# Power-Conversion.net
KiCad netlist of a schematic drawn in EAGLE
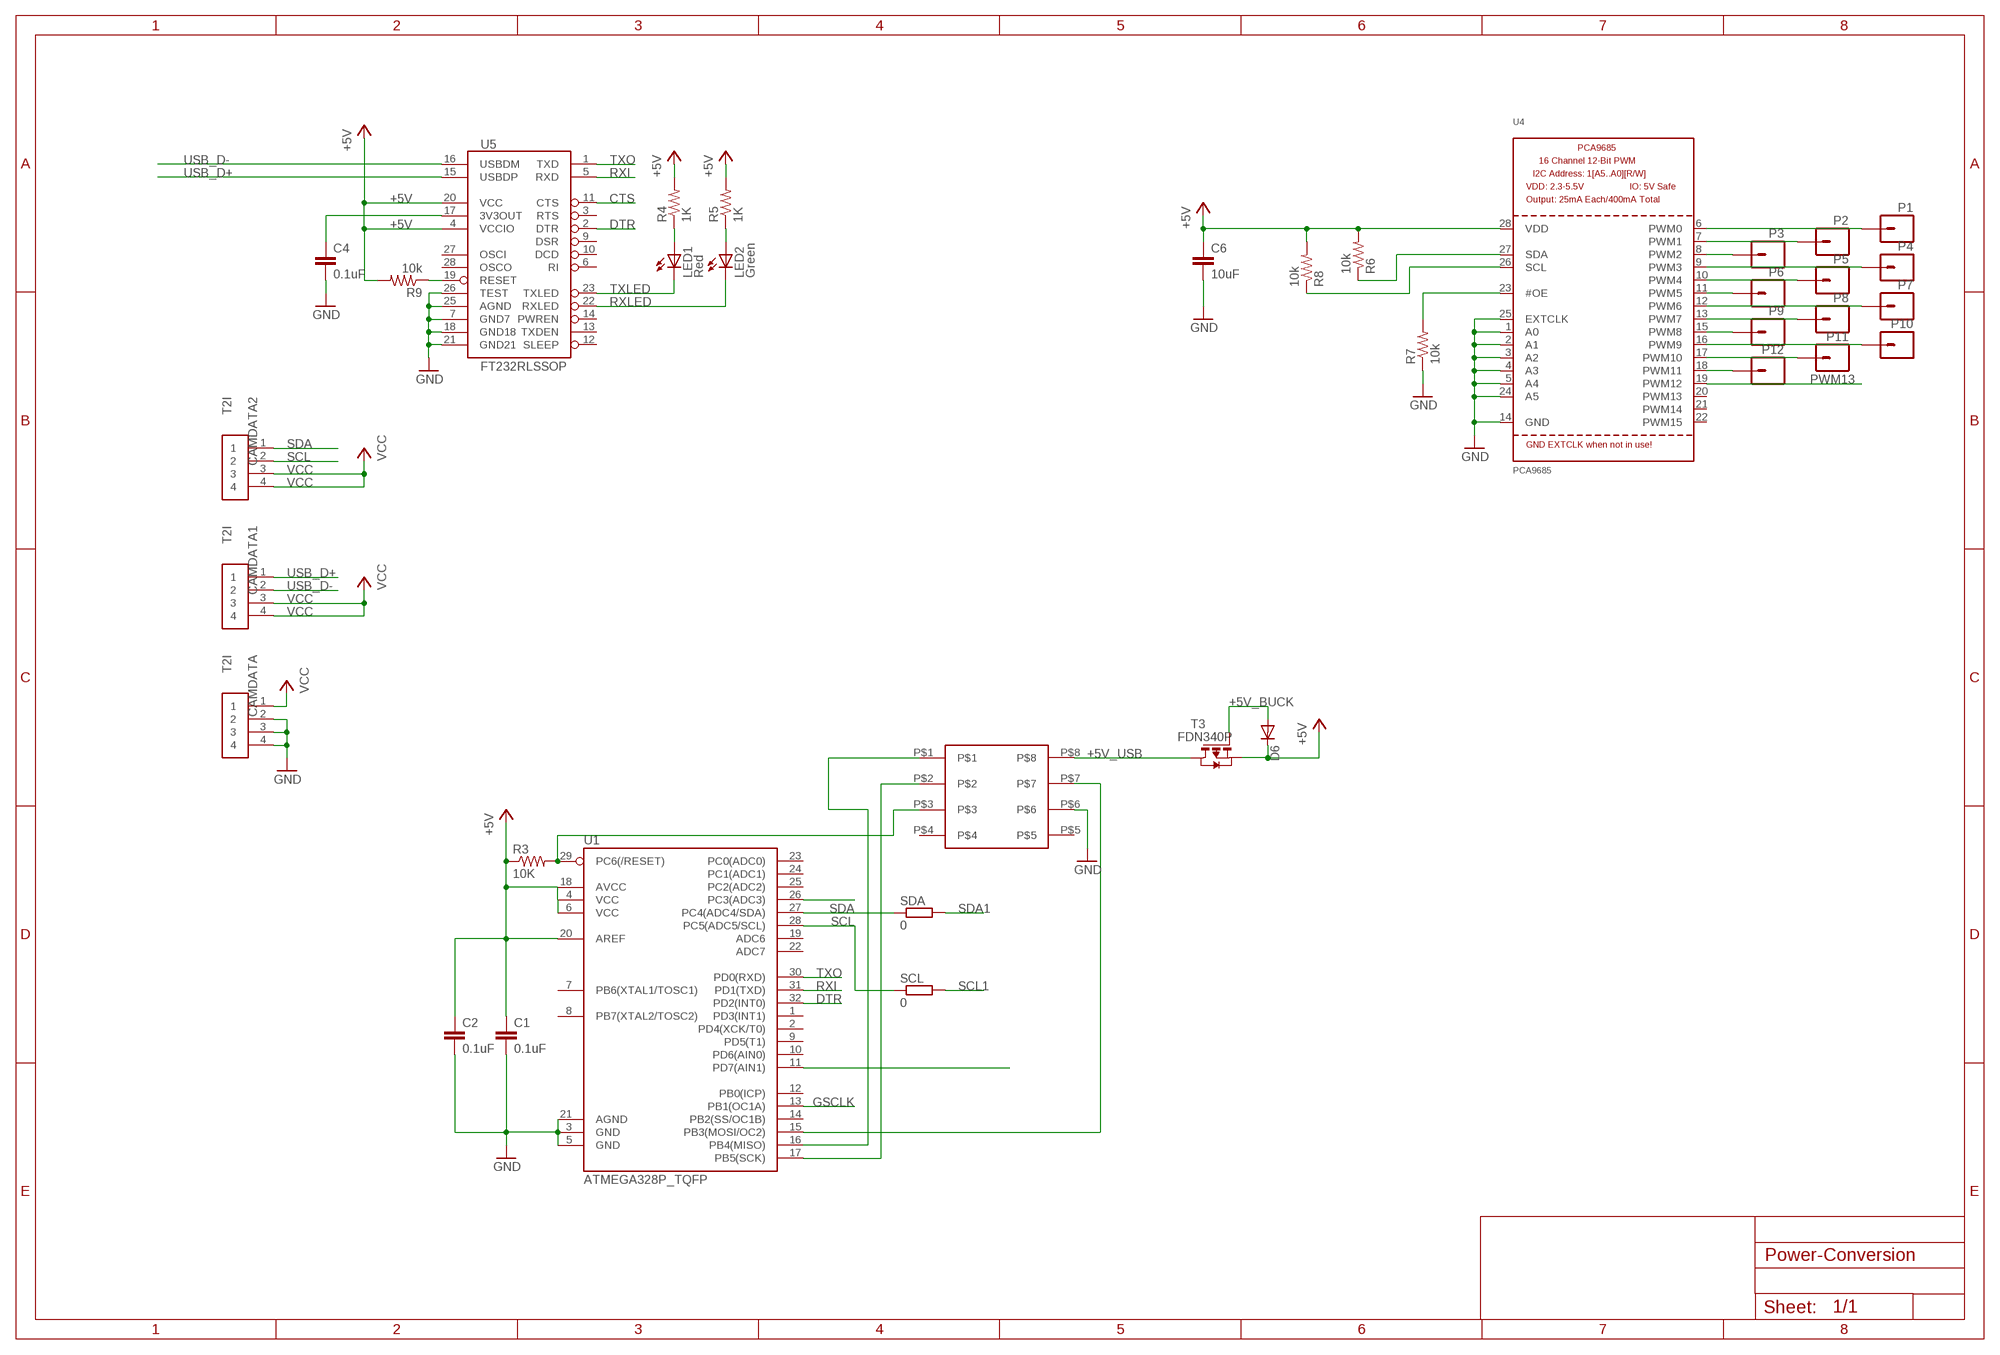
[diagram p0: schematic, sheet 1, part 1 of 2]
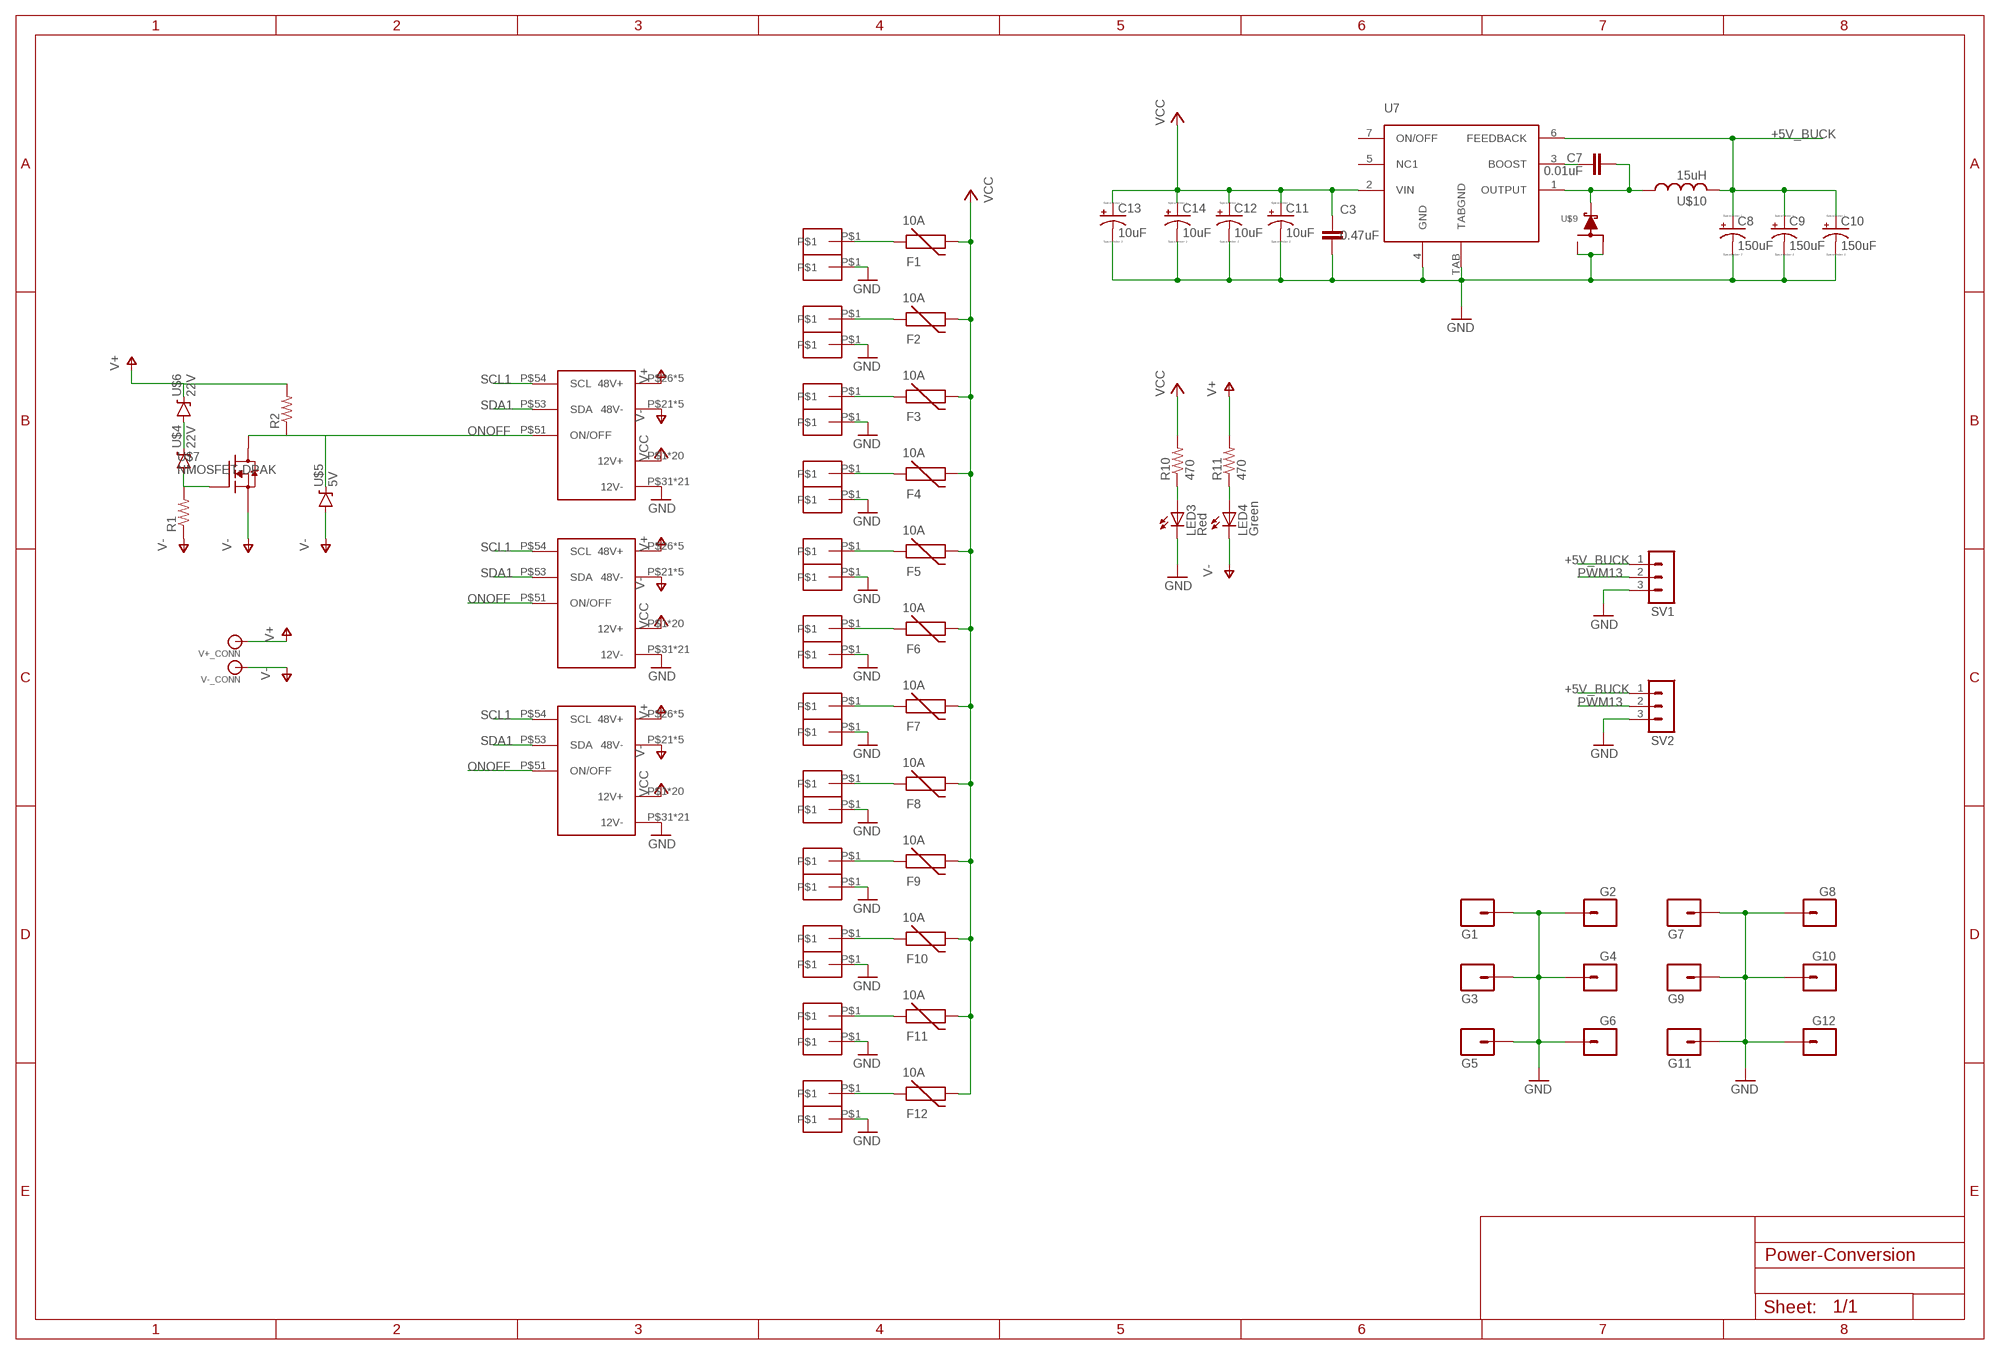
[diagram p1: schematic, sheet 1, part 2 of 2]

(export (version "E")
  (design (tool "Eeschema 10.0.6"))
  (components
    (comp (ref "C1")
      (value "0.1uF")
      (footprint "eagle-import:0603-CAP")
      (libsource (lib "eagle-import") (part "0.1UF-25V(+80/-20%)(0603)"))
    )
    (comp (ref "C2")
      (value "0.1uF")
      (footprint "eagle-import:0603-CAP")
      (libsource (lib "eagle-import") (part "0.1UF-25V(+80/-20%)(0603)"))
    )
    (comp (ref "C3")
      (value "0.47uF")
      (footprint "eagle-import:C0603")
      (libsource (lib "eagle-import") (part "C-EUC0603"))
    )
    (comp (ref "C4")
      (value "0.1uF")
      (footprint "eagle-import:0603-CAP")
      (libsource (lib "eagle-import") (part "0.1UF-25V(+80/-20%)(0603)"))
    )
    (comp (ref "C6")
      (value "10uF")
      (footprint "eagle-import:0603-CAP")
      (libsource (lib "eagle-import") (part "0.1UF-25V(+80/-20%)(0603)"))
    )
    (comp (ref "C7")
      (value "0.01uF")
      (footprint "eagle-import:0603-CAP")
      (libsource (lib "eagle-import") (part "CAP0603-CAP"))
    )
    (comp (ref "C8")
      (value "150uF")
      (footprint "eagle-import:CTAN(7.30_4.30MM)")
      (libsource (lib "eagle-import") (part "C-TANTALUM(10UF_150UF)"))
    )
    (comp (ref "C9")
      (value "150uF")
      (footprint "eagle-import:CTAN(7.30_4.30MM)")
      (libsource (lib "eagle-import") (part "C-TANTALUM(10UF_150UF)"))
    )
    (comp (ref "C10")
      (value "150uF")
      (footprint "eagle-import:CTAN(7.30_4.30MM)")
      (libsource (lib "eagle-import") (part "C-TANTALUM(10UF_150UF)"))
    )
    (comp (ref "C11")
      (value "10uF")
      (footprint "eagle-import:CTAN(7.30_4.30MM)")
      (libsource (lib "eagle-import") (part "C-TANTALUM(10UF_150UF)"))
    )
    (comp (ref "C12")
      (value "10uF")
      (footprint "eagle-import:CTAN(7.30_4.30MM)")
      (libsource (lib "eagle-import") (part "C-TANTALUM(10UF_150UF)"))
    )
    (comp (ref "C13")
      (value "10uF")
      (footprint "eagle-import:CTAN(7.30_4.30MM)")
      (libsource (lib "eagle-import") (part "C-TANTALUM(10UF_150UF)"))
    )
    (comp (ref "C14")
      (value "10uF")
      (footprint "eagle-import:CTAN(7.30_4.30MM)")
      (libsource (lib "eagle-import") (part "C-TANTALUM(10UF_150UF)"))
    )
    (comp (ref "CAMDATA")
      (value "T2I")
      (footprint "eagle-import:T2I")
      (libsource (lib "eagle-import") (part "T2I"))
    )
    (comp (ref "CAMDATA1")
      (value "T2I")
      (footprint "eagle-import:T2I")
      (libsource (lib "eagle-import") (part "T2I"))
    )
    (comp (ref "CAMDATA2")
      (value "T2I")
      (footprint "eagle-import:T2I")
      (libsource (lib "eagle-import") (part "T2I"))
    )
    (comp (ref "D6")
      (value "DIODE-DO-214AC")
      (footprint "eagle-import:DO-214AC")
      (libsource (lib "eagle-import") (part "DIODE-DO-214AC"))
    )
    (comp (ref "F1")
      (value "10A")
      (footprint "eagle-import:PTC-2920")
      (libsource (lib "eagle-import") (part "PTC(2920L)"))
    )
    (comp (ref "F2")
      (value "10A")
      (footprint "eagle-import:PTC-2920")
      (libsource (lib "eagle-import") (part "PTC(2920L)"))
    )
    (comp (ref "F3")
      (value "10A")
      (footprint "eagle-import:PTC-2920")
      (libsource (lib "eagle-import") (part "PTC(2920L)"))
    )
    (comp (ref "F4")
      (value "10A")
      (footprint "eagle-import:PTC-2920")
      (libsource (lib "eagle-import") (part "PTC(2920L)"))
    )
    (comp (ref "F5")
      (value "10A")
      (footprint "eagle-import:PTC-2920")
      (libsource (lib "eagle-import") (part "PTC(2920L)"))
    )
    (comp (ref "F6")
      (value "10A")
      (footprint "eagle-import:PTC-2920")
      (libsource (lib "eagle-import") (part "PTC(2920L)"))
    )
    (comp (ref "F7")
      (value "10A")
      (footprint "eagle-import:PTC-2920")
      (libsource (lib "eagle-import") (part "PTC(2920L)"))
    )
    (comp (ref "F8")
      (value "10A")
      (footprint "eagle-import:PTC-2920")
      (libsource (lib "eagle-import") (part "PTC(2920L)"))
    )
    (comp (ref "F9")
      (value "10A")
      (footprint "eagle-import:PTC-2920")
      (libsource (lib "eagle-import") (part "PTC(2920L)"))
    )
    (comp (ref "F10")
      (value "10A")
      (footprint "eagle-import:PTC-2920")
      (libsource (lib "eagle-import") (part "PTC(2920L)"))
    )
    (comp (ref "F11")
      (value "10A")
      (footprint "eagle-import:PTC-2920")
      (libsource (lib "eagle-import") (part "PTC(2920L)"))
    )
    (comp (ref "F12")
      (value "10A")
      (footprint "eagle-import:PTC-2920")
      (libsource (lib "eagle-import") (part "PTC(2920L)"))
    )
    (comp (ref "G1")
      (value "M01PTH")
      (footprint "eagle-import:1X01")
      (libsource (lib "eagle-import") (part "M01PTH"))
    )
    (comp (ref "G2")
      (value "M01PTH")
      (footprint "eagle-import:1X01")
      (libsource (lib "eagle-import") (part "M01PTH"))
    )
    (comp (ref "G3")
      (value "M01PTH")
      (footprint "eagle-import:1X01")
      (libsource (lib "eagle-import") (part "M01PTH"))
    )
    (comp (ref "G4")
      (value "M01PTH")
      (footprint "eagle-import:1X01")
      (libsource (lib "eagle-import") (part "M01PTH"))
    )
    (comp (ref "G5")
      (value "M01PTH")
      (footprint "eagle-import:1X01")
      (libsource (lib "eagle-import") (part "M01PTH"))
    )
    (comp (ref "G6")
      (value "M01PTH")
      (footprint "eagle-import:1X01")
      (libsource (lib "eagle-import") (part "M01PTH"))
    )
    (comp (ref "G7")
      (value "M01PTH")
      (footprint "eagle-import:1X01")
      (libsource (lib "eagle-import") (part "M01PTH"))
    )
    (comp (ref "G8")
      (value "M01PTH")
      (footprint "eagle-import:1X01")
      (libsource (lib "eagle-import") (part "M01PTH"))
    )
    (comp (ref "G9")
      (value "M01PTH")
      (footprint "eagle-import:1X01")
      (libsource (lib "eagle-import") (part "M01PTH"))
    )
    (comp (ref "G10")
      (value "M01PTH")
      (footprint "eagle-import:1X01")
      (libsource (lib "eagle-import") (part "M01PTH"))
    )
    (comp (ref "G11")
      (value "M01PTH")
      (footprint "eagle-import:1X01")
      (libsource (lib "eagle-import") (part "M01PTH"))
    )
    (comp (ref "G12")
      (value "M01PTH")
      (footprint "eagle-import:1X01")
      (libsource (lib "eagle-import") (part "M01PTH"))
    )
    (comp (ref "LED1")
      (value "Red")
      (footprint "eagle-import:LED-0603")
      (libsource (lib "eagle-import") (part "LED0603"))
    )
    (comp (ref "LED2")
      (value "Green")
      (footprint "eagle-import:LED-0603")
      (libsource (lib "eagle-import") (part "LED0603"))
    )
    (comp (ref "LED3")
      (value "Red")
      (footprint "eagle-import:LED-0603")
      (libsource (lib "eagle-import") (part "LED0603"))
    )
    (comp (ref "LED4")
      (value "Green")
      (footprint "eagle-import:LED-0603")
      (libsource (lib "eagle-import") (part "LED0603"))
    )
    (comp (ref "P1")
      (value "M01PTH")
      (footprint "eagle-import:1X01")
      (libsource (lib "eagle-import") (part "M01PTH"))
    )
    (comp (ref "P2")
      (value "M01PTH")
      (footprint "eagle-import:1X01")
      (libsource (lib "eagle-import") (part "M01PTH"))
    )
    (comp (ref "P3")
      (value "M01PTH")
      (footprint "eagle-import:1X01")
      (libsource (lib "eagle-import") (part "M01PTH"))
    )
    (comp (ref "P4")
      (value "M01PTH")
      (footprint "eagle-import:1X01")
      (libsource (lib "eagle-import") (part "M01PTH"))
    )
    (comp (ref "P5")
      (value "M01PTH")
      (footprint "eagle-import:1X01")
      (libsource (lib "eagle-import") (part "M01PTH"))
    )
    (comp (ref "P6")
      (value "M01PTH")
      (footprint "eagle-import:1X01")
      (libsource (lib "eagle-import") (part "M01PTH"))
    )
    (comp (ref "P7")
      (value "M01PTH")
      (footprint "eagle-import:1X01")
      (libsource (lib "eagle-import") (part "M01PTH"))
    )
    (comp (ref "P8")
      (value "M01PTH")
      (footprint "eagle-import:1X01")
      (libsource (lib "eagle-import") (part "M01PTH"))
    )
    (comp (ref "P9")
      (value "M01PTH")
      (footprint "eagle-import:1X01")
      (libsource (lib "eagle-import") (part "M01PTH"))
    )
    (comp (ref "P10")
      (value "M01PTH")
      (footprint "eagle-import:1X01")
      (libsource (lib "eagle-import") (part "M01PTH"))
    )
    (comp (ref "P11")
      (value "M01PTH")
      (footprint "eagle-import:1X01")
      (libsource (lib "eagle-import") (part "M01PTH"))
    )
    (comp (ref "P12")
      (value "M01PTH")
      (footprint "eagle-import:1X01")
      (libsource (lib "eagle-import") (part "M01PTH"))
    )
    (comp (ref "R1")
      (value "RESISTOR0603-RES")
      (footprint "eagle-import:0603-RES")
      (libsource (lib "eagle-import") (part "SparkFun-Passives_RESISTOR0603-RES"))
    )
    (comp (ref "R2")
      (value "RESISTOR0603-RES")
      (footprint "eagle-import:0603-RES")
      (libsource (lib "eagle-import") (part "SparkFun-Passives_RESISTOR0603-RES"))
    )
    (comp (ref "R3")
      (value "10K")
      (footprint "eagle-import:0603-RES")
      (libsource (lib "eagle-import") (part "10KOHM-1/10W-1%(0603)0603"))
    )
    (comp (ref "R4")
      (value "1K")
      (footprint "eagle-import:R0603")
      (libsource (lib "eagle-import") (part "R-US_R0603"))
    )
    (comp (ref "R5")
      (value "1K")
      (footprint "eagle-import:R0603")
      (libsource (lib "eagle-import") (part "R-US_R0603"))
    )
    (comp (ref "R6")
      (value "10k")
      (footprint "eagle-import:0603-RES")
      (libsource (lib "eagle-import") (part "470OHM1/10W1%(0603)"))
    )
    (comp (ref "R7")
      (value "10k")
      (footprint "eagle-import:0603-RES")
      (libsource (lib "eagle-import") (part "470OHM1/10W1%(0603)"))
    )
    (comp (ref "R8")
      (value "10k")
      (footprint "eagle-import:0603-RES")
      (libsource (lib "eagle-import") (part "470OHM1/10W1%(0603)"))
    )
    (comp (ref "R9")
      (value "10k")
      (footprint "eagle-import:0402-RES")
      (libsource (lib "eagle-import") (part "RESISTOR0402-RES"))
    )
    (comp (ref "R10")
      (value "470")
      (footprint "eagle-import:R0603")
      (libsource (lib "eagle-import") (part "R-US_R0603"))
    )
    (comp (ref "R11")
      (value "470")
      (footprint "eagle-import:R0603")
      (libsource (lib "eagle-import") (part "R-US_R0603"))
    )
    (comp (ref "SCL")
      (value "0")
      (footprint "eagle-import:R0603")
      (libsource (lib "eagle-import") (part "R-EU_R0603"))
    )
    (comp (ref "SDA")
      (value "0")
      (footprint "eagle-import:R0603")
      (libsource (lib "eagle-import") (part "R-EU_R0603"))
    )
    (comp (ref "SV1")
      (value "MA03-1")
      (footprint "eagle-import:MA03-1")
      (libsource (lib "eagle-import") (part "MA03-1"))
    )
    (comp (ref "SV2")
      (value "MA03-1")
      (footprint "eagle-import:MA03-1")
      (libsource (lib "eagle-import") (part "MA03-1"))
    )
    (comp (ref "T3")
      (value "FDN340P")
      (footprint "eagle-import:SOT-23")
      (libsource (lib "eagle-import") (part "FDN340P"))
    )
    (comp (ref "U$1")
      (value "POWER-BRICK-CONNECTOR")
      (footprint "eagle-import:POWER-BRICK-CONNECTOR")
      (libsource (lib "eagle-import") (part "POWER-BRICK-CONNECTOR"))
    )
    (comp (ref "U$2")
      (value "POWER-BRICK-CONNECTOR")
      (footprint "eagle-import:POWER-BRICK-CONNECTOR")
      (libsource (lib "eagle-import") (part "POWER-BRICK-CONNECTOR"))
    )
    (comp (ref "U$3")
      (value "POWER-BRICK-CONNECTOR")
      (footprint "eagle-import:POWER-BRICK-CONNECTOR")
      (libsource (lib "eagle-import") (part "POWER-BRICK-CONNECTOR"))
    )
    (comp (ref "U$4")
      (value "22V")
      (footprint "eagle-import:SOT23-3")
      (libsource (lib "eagle-import") (part "ZENER-SOT23"))
    )
    (comp (ref "U$5")
      (value "5V")
      (footprint "eagle-import:SOT23-3")
      (libsource (lib "eagle-import") (part "ZENER-SOT23"))
    )
    (comp (ref "U$6")
      (value "22V")
      (footprint "eagle-import:SOT23-3")
      (libsource (lib "eagle-import") (part "ZENER-SOT23"))
    )
    (comp (ref "U$7")
      (value "NMOSFET-DPAK")
      (footprint "eagle-import:DPAK")
      (libsource (lib "eagle-import") (part "NMOSFET-DPAK"))
    )
    (comp (ref "U$8")
      (value "8_PIN_HEADER")
      (footprint "eagle-import:8_PIN_HEADER")
      (libsource (lib "eagle-import") (part "8_PIN_HEADER"))
    )
    (comp (ref "U$9")
      (value "SWITCHMODE_SCHOTTKY")
      (footprint "eagle-import:DPAK-3")
      (libsource (lib "eagle-import") (part "SWITCHMODE_SCHOTTKY"))
    )
    (comp (ref "U$10")
      (value "15uH")
      (footprint "eagle-import:HCMA1305")
      (libsource (lib "eagle-import") (part "HCMA1305"))
    )
    (comp (ref "U1")
      (value "ATMEGA328P_TQFP")
      (footprint "eagle-import:TQFP32-08")
      (libsource (lib "eagle-import") (part "ATMEGA328P_TQFP"))
    )
    (comp (ref "U4")
      (value "PCA9685")
      (footprint "eagle-import:TSSOP28")
      (libsource (lib "eagle-import") (part "PCA9685"))
    )
    (comp (ref "U5")
      (value "FT232RLSSOP")
      (footprint "eagle-import:SSOP28DB")
      (libsource (lib "eagle-import") (part "FT232RLSSOP"))
    )
    (comp (ref "U7")
      (value "LM2678")
      (footprint "eagle-import:LM2678")
      (libsource (lib "eagle-import") (part "LM2678"))
    )
    (comp (ref "V+_CONN")
      (value "BANANA_CONN")
      (footprint "eagle-import:BANANA_CONN")
      (libsource (lib "eagle-import") (part "BANANA_CONN"))
    )
    (comp (ref "V+_ESC1")
      (value "16_GUAGE_WIRE")
      (footprint "eagle-import:16_GUAGE_WIRE")
      (libsource (lib "eagle-import") (part "16_GUAGE_WIRE"))
    )
    (comp (ref "V+_ESC2")
      (value "16_GUAGE_WIRE")
      (footprint "eagle-import:16_GUAGE_WIRE")
      (libsource (lib "eagle-import") (part "16_GUAGE_WIRE"))
    )
    (comp (ref "V+_ESC3")
      (value "16_GUAGE_WIRE")
      (footprint "eagle-import:16_GUAGE_WIRE")
      (libsource (lib "eagle-import") (part "16_GUAGE_WIRE"))
    )
    (comp (ref "V+_ESC4")
      (value "16_GUAGE_WIRE")
      (footprint "eagle-import:16_GUAGE_WIRE")
      (libsource (lib "eagle-import") (part "16_GUAGE_WIRE"))
    )
    (comp (ref "V+_ESC5")
      (value "16_GUAGE_WIRE")
      (footprint "eagle-import:16_GUAGE_WIRE")
      (libsource (lib "eagle-import") (part "16_GUAGE_WIRE"))
    )
    (comp (ref "V+_ESC6")
      (value "16_GUAGE_WIRE")
      (footprint "eagle-import:16_GUAGE_WIRE")
      (libsource (lib "eagle-import") (part "16_GUAGE_WIRE"))
    )
    (comp (ref "V+_ESC7")
      (value "16_GUAGE_WIRE")
      (footprint "eagle-import:16_GUAGE_WIRE")
      (libsource (lib "eagle-import") (part "16_GUAGE_WIRE"))
    )
    (comp (ref "V+_ESC8")
      (value "16_GUAGE_WIRE")
      (footprint "eagle-import:16_GUAGE_WIRE")
      (libsource (lib "eagle-import") (part "16_GUAGE_WIRE"))
    )
    (comp (ref "V+_ESC9")
      (value "16_GUAGE_WIRE")
      (footprint "eagle-import:16_GUAGE_WIRE")
      (libsource (lib "eagle-import") (part "16_GUAGE_WIRE"))
    )
    (comp (ref "V+_ESC10")
      (value "16_GUAGE_WIRE")
      (footprint "eagle-import:16_GUAGE_WIRE")
      (libsource (lib "eagle-import") (part "16_GUAGE_WIRE"))
    )
    (comp (ref "V+_ESC11")
      (value "16_GUAGE_WIRE")
      (footprint "eagle-import:16_GUAGE_WIRE")
      (libsource (lib "eagle-import") (part "16_GUAGE_WIRE"))
    )
    (comp (ref "V+_ESC12")
      (value "16_GUAGE_WIRE")
      (footprint "eagle-import:16_GUAGE_WIRE")
      (libsource (lib "eagle-import") (part "16_GUAGE_WIRE"))
    )
    (comp (ref "V-_CONN")
      (value "BANANA_CONN")
      (footprint "eagle-import:BANANA_CONN")
      (libsource (lib "eagle-import") (part "BANANA_CONN"))
    )
    (comp (ref "V-_ESC1")
      (value "16_GUAGE_WIRE")
      (footprint "eagle-import:16_GUAGE_WIRE")
      (libsource (lib "eagle-import") (part "16_GUAGE_WIRE"))
    )
    (comp (ref "V-_ESC2")
      (value "16_GUAGE_WIRE")
      (footprint "eagle-import:16_GUAGE_WIRE")
      (libsource (lib "eagle-import") (part "16_GUAGE_WIRE"))
    )
    (comp (ref "V-_ESC3")
      (value "16_GUAGE_WIRE")
      (footprint "eagle-import:16_GUAGE_WIRE")
      (libsource (lib "eagle-import") (part "16_GUAGE_WIRE"))
    )
    (comp (ref "V-_ESC4")
      (value "16_GUAGE_WIRE")
      (footprint "eagle-import:16_GUAGE_WIRE")
      (libsource (lib "eagle-import") (part "16_GUAGE_WIRE"))
    )
    (comp (ref "V-_ESC5")
      (value "16_GUAGE_WIRE")
      (footprint "eagle-import:16_GUAGE_WIRE")
      (libsource (lib "eagle-import") (part "16_GUAGE_WIRE"))
    )
    (comp (ref "V-_ESC6")
      (value "16_GUAGE_WIRE")
      (footprint "eagle-import:16_GUAGE_WIRE")
      (libsource (lib "eagle-import") (part "16_GUAGE_WIRE"))
    )
    (comp (ref "V-_ESC7")
      (value "16_GUAGE_WIRE")
      (footprint "eagle-import:16_GUAGE_WIRE")
      (libsource (lib "eagle-import") (part "16_GUAGE_WIRE"))
    )
    (comp (ref "V-_ESC8")
      (value "16_GUAGE_WIRE")
      (footprint "eagle-import:16_GUAGE_WIRE")
      (libsource (lib "eagle-import") (part "16_GUAGE_WIRE"))
    )
    (comp (ref "V-_ESC9")
      (value "16_GUAGE_WIRE")
      (footprint "eagle-import:16_GUAGE_WIRE")
      (libsource (lib "eagle-import") (part "16_GUAGE_WIRE"))
    )
    (comp (ref "V-_ESC10")
      (value "16_GUAGE_WIRE")
      (footprint "eagle-import:16_GUAGE_WIRE")
      (libsource (lib "eagle-import") (part "16_GUAGE_WIRE"))
    )
    (comp (ref "V-_ESC11")
      (value "16_GUAGE_WIRE")
      (footprint "eagle-import:16_GUAGE_WIRE")
      (libsource (lib "eagle-import") (part "16_GUAGE_WIRE"))
    )
    (comp (ref "V-_ESC12")
      (value "16_GUAGE_WIRE")
      (footprint "eagle-import:16_GUAGE_WIRE")
      (libsource (lib "eagle-import") (part "16_GUAGE_WIRE"))
    )
  )
  (nets
    (net (code "1") (name "+5V") (class "Default")
      (node (ref "C1") (pin "1") (pinfunction "1_1") (pintype "passive"))
      (node (ref "C2") (pin "1") (pinfunction "1_1") (pintype "passive"))
      (node (ref "C6") (pin "1") (pinfunction "1_1") (pintype "passive"))
      (node (ref "D6") (pin "C") (pinfunction "C_C") (pintype "passive"))
      (node (ref "R3") (pin "1") (pinfunction "1_1") (pintype "passive"))
      (node (ref "R4") (pin "2") (pinfunction "2_2") (pintype "passive"))
      (node (ref "R5") (pin "2") (pinfunction "2_2") (pintype "passive"))
      (node (ref "R6") (pin "2") (pinfunction "2_2") (pintype "passive"))
      (node (ref "R8") (pin "2") (pinfunction "2_2") (pintype "passive"))
      (node (ref "R9") (pin "2") (pinfunction "2_2") (pintype "passive"))
      (node (ref "T3") (pin "2") (pinfunction "S_2") (pintype "passive"))
      (node (ref "U1") (pin "18") (pinfunction "AVCC_18") (pintype "bidirectional"))
      (node (ref "U1") (pin "20") (pinfunction "AREF_20") (pintype "bidirectional"))
      (node (ref "U1") (pin "4") (pinfunction "VCC_4") (pintype "bidirectional"))
      (node (ref "U1") (pin "6") (pinfunction "VCC_6") (pintype "bidirectional"))
      (node (ref "U4") (pin "28") (pinfunction "VDD_28") (pintype "power_in"))
      (node (ref "U5") (pin "20") (pinfunction "VCC_20") (pintype "power_in"))
      (node (ref "U5") (pin "4") (pinfunction "VCCIO_4") (pintype "power_in"))
    )
    (net (code "2") (name "/+5V_BUCK") (class "Default")
      (node (ref "C10") (pin "+") (pinfunction "+_+") (pintype "passive"))
      (node (ref "C8") (pin "+") (pinfunction "+_+") (pintype "passive"))
      (node (ref "C9") (pin "+") (pinfunction "+_+") (pintype "passive"))
      (node (ref "D6") (pin "A") (pinfunction "A_A") (pintype "passive"))
      (node (ref "SV1") (pin "1") (pinfunction "1_1") (pintype "passive"))
      (node (ref "SV2") (pin "1") (pinfunction "1_1") (pintype "passive"))
      (node (ref "T3") (pin "3") (pinfunction "G_3") (pintype "passive"))
      (node (ref "U$10") (pin "P$2") (pinfunction "2_P$2") (pintype "passive"))
      (node (ref "U7") (pin "6") (pinfunction "FEEDBACK_6") (pintype "bidirectional"))
    )
    (net (code "3") (name "/+5V_USB") (class "Default")
      (node (ref "T3") (pin "1") (pinfunction "D_1") (pintype "passive"))
      (node (ref "U$8") (pin "P$8") (pinfunction "P$8_P$8") (pintype "bidirectional"))
    )
    (net (code "4") (name "/CTS") (class "Default")
      (node (ref "U1") (pin "26") (pinfunction "PC3(ADC3)_26") (pintype "bidirectional"))
      (node (ref "U5") (pin "11") (pinfunction "CTS_11") (pintype "input"))
    )
    (net (code "5") (name "/DTR") (class "Default")
      (node (ref "U1") (pin "32") (pinfunction "PD2(INT0)_32") (pintype "bidirectional"))
      (node (ref "U5") (pin "2") (pinfunction "DTR_2") (pintype "output"))
    )
    (net (code "6") (name "/GSCLK") (class "Default")
      (node (ref "U1") (pin "13") (pinfunction "PB1(OC1A)_13") (pintype "bidirectional"))
    )
    (net (code "7") (name "/ONOFF") (class "Default")
      (node (ref "R2") (pin "1") (pinfunction "1_1") (pintype "passive"))
      (node (ref "U$1") (pin "P$51") (pinfunction "ON/OFF_P$51") (pintype "bidirectional"))
      (node (ref "U$2") (pin "P$51") (pinfunction "ON/OFF_P$51") (pintype "bidirectional"))
      (node (ref "U$3") (pin "P$51") (pinfunction "ON/OFF_P$51") (pintype "bidirectional"))
      (node (ref "U$5") (pin "3") (pinfunction "C_3") (pintype "passive"))
      (node (ref "U$7") (pin "4") (pinfunction "D1_4") (pintype "passive"))
    )
    (net (code "8") (name "/PWM13") (class "Default")
      (node (ref "SV1") (pin "2") (pinfunction "2_2") (pintype "passive"))
      (node (ref "SV2") (pin "2") (pinfunction "2_2") (pintype "passive"))
      (node (ref "U4") (pin "19") (pinfunction "PWM12_19") (pintype "output"))
    )
    (net (code "9") (name "/RXI") (class "Default")
      (node (ref "U1") (pin "31") (pinfunction "PD1(TXD)_31") (pintype "bidirectional"))
      (node (ref "U5") (pin "5") (pinfunction "RXD_5") (pintype "input"))
    )
    (net (code "10") (name "/RXLED") (class "Default")
      (node (ref "LED2") (pin "C") (pinfunction "C_C") (pintype "passive"))
      (node (ref "U5") (pin "22") (pinfunction "RXLED_22") (pintype "input"))
    )
    (net (code "11") (name "/SCL") (class "Default")
      (node (ref "CAMDATA2") (pin "2") (pinfunction "2_2") (pintype "bidirectional"))
      (node (ref "R8") (pin "1") (pinfunction "1_1") (pintype "passive"))
      (node (ref "SCL") (pin "1") (pinfunction "1_1") (pintype "passive"))
      (node (ref "U1") (pin "28") (pinfunction "PC5(ADC5/SCL)_28") (pintype "bidirectional"))
      (node (ref "U4") (pin "26") (pinfunction "SCL_26") (pintype "bidirectional"))
    )
    (net (code "12") (name "/SCL1") (class "Default")
      (node (ref "SCL") (pin "2") (pinfunction "2_2") (pintype "passive"))
      (node (ref "U$1") (pin "P$54") (pinfunction "SCL_P$54") (pintype "bidirectional"))
      (node (ref "U$2") (pin "P$54") (pinfunction "SCL_P$54") (pintype "bidirectional"))
      (node (ref "U$3") (pin "P$54") (pinfunction "SCL_P$54") (pintype "bidirectional"))
    )
    (net (code "13") (name "/SDA") (class "Default")
      (node (ref "CAMDATA2") (pin "1") (pinfunction "1_1") (pintype "bidirectional"))
      (node (ref "R6") (pin "1") (pinfunction "1_1") (pintype "passive"))
      (node (ref "SDA") (pin "1") (pinfunction "1_1") (pintype "passive"))
      (node (ref "U1") (pin "27") (pinfunction "PC4(ADC4/SDA)_27") (pintype "bidirectional"))
      (node (ref "U4") (pin "27") (pinfunction "SDA_27") (pintype "bidirectional"))
    )
    (net (code "14") (name "/SDA1") (class "Default")
      (node (ref "SDA") (pin "2") (pinfunction "2_2") (pintype "passive"))
      (node (ref "U$1") (pin "P$53") (pinfunction "SDA_P$53") (pintype "bidirectional"))
      (node (ref "U$2") (pin "P$53") (pinfunction "SDA_P$53") (pintype "bidirectional"))
      (node (ref "U$3") (pin "P$53") (pinfunction "SDA_P$53") (pintype "bidirectional"))
    )
    (net (code "15") (name "/TXLED") (class "Default")
      (node (ref "LED1") (pin "C") (pinfunction "C_C") (pintype "passive"))
      (node (ref "U5") (pin "23") (pinfunction "TXLED_23") (pintype "input"))
    )
    (net (code "16") (name "/TXO") (class "Default")
      (node (ref "U1") (pin "30") (pinfunction "PD0(RXD)_30") (pintype "bidirectional"))
      (node (ref "U5") (pin "1") (pinfunction "TXD_1") (pintype "output"))
    )
    (net (code "17") (name "/USB_D+") (class "Default")
      (node (ref "CAMDATA1") (pin "1") (pinfunction "1_1") (pintype "bidirectional"))
      (node (ref "U5") (pin "15") (pinfunction "USBDP_15") (pintype "bidirectional"))
    )
    (net (code "18") (name "/USB_D-") (class "Default")
      (node (ref "CAMDATA1") (pin "2") (pinfunction "2_2") (pintype "bidirectional"))
      (node (ref "U5") (pin "16") (pinfunction "USBDM_16") (pintype "bidirectional"))
    )
    (net (code "19") (name "GND") (class "Default")
      (node (ref "C1") (pin "2") (pinfunction "2_2") (pintype "passive"))
      (node (ref "C10") (pin "-") (pinfunction "-_-") (pintype "passive"))
      (node (ref "C11") (pin "-") (pinfunction "-_-") (pintype "passive"))
      (node (ref "C12") (pin "-") (pinfunction "-_-") (pintype "passive"))
      (node (ref "C13") (pin "-") (pinfunction "-_-") (pintype "passive"))
      (node (ref "C14") (pin "-") (pinfunction "-_-") (pintype "passive"))
      (node (ref "C2") (pin "2") (pinfunction "2_2") (pintype "passive"))
      (node (ref "C3") (pin "2") (pinfunction "2_2") (pintype "passive"))
      (node (ref "C4") (pin "2") (pinfunction "2_2") (pintype "passive"))
      (node (ref "C6") (pin "2") (pinfunction "2_2") (pintype "passive"))
      (node (ref "C8") (pin "-") (pinfunction "-_-") (pintype "passive"))
      (node (ref "C9") (pin "-") (pinfunction "-_-") (pintype "passive"))
      (node (ref "CAMDATA") (pin "2") (pinfunction "2_2") (pintype "bidirectional"))
      (node (ref "CAMDATA") (pin "3") (pinfunction "3_3") (pintype "bidirectional"))
      (node (ref "CAMDATA") (pin "4") (pinfunction "4_4") (pintype "bidirectional"))
      (node (ref "G1") (pin "1") (pinfunction "1_1") (pintype "passive"))
      (node (ref "G10") (pin "1") (pinfunction "1_1") (pintype "passive"))
      (node (ref "G11") (pin "1") (pinfunction "1_1") (pintype "passive"))
      (node (ref "G12") (pin "1") (pinfunction "1_1") (pintype "passive"))
      (node (ref "G2") (pin "1") (pinfunction "1_1") (pintype "passive"))
      (node (ref "G3") (pin "1") (pinfunction "1_1") (pintype "passive"))
      (node (ref "G4") (pin "1") (pinfunction "1_1") (pintype "passive"))
      (node (ref "G5") (pin "1") (pinfunction "1_1") (pintype "passive"))
      (node (ref "G6") (pin "1") (pinfunction "1_1") (pintype "passive"))
      (node (ref "G7") (pin "1") (pinfunction "1_1") (pintype "passive"))
      (node (ref "G8") (pin "1") (pinfunction "1_1") (pintype "passive"))
      (node (ref "G9") (pin "1") (pinfunction "1_1") (pintype "passive"))
      (node (ref "LED3") (pin "C") (pinfunction "C_C") (pintype "passive"))
      (node (ref "R7") (pin "1") (pinfunction "1_1") (pintype "passive"))
      (node (ref "SV1") (pin "3") (pinfunction "3_3") (pintype "passive"))
      (node (ref "SV2") (pin "3") (pinfunction "3_3") (pintype "passive"))
      (node (ref "U$1") (pin "P$31") (pinfunction "12V-_P$31") (pintype "bidirectional"))
      (node (ref "U$1") (pin "P$32") (pinfunction "12V-_P$32") (pintype "bidirectional"))
      (node (ref "U$1") (pin "P$33") (pinfunction "12V-_P$33") (pintype "bidirectional"))
      (node (ref "U$1") (pin "P$34") (pinfunction "12V-_P$34") (pintype "bidirectional"))
      (node (ref "U$1") (pin "P$35") (pinfunction "12V-_P$35") (pintype "bidirectional"))
      (node (ref "U$1") (pin "P$36") (pinfunction "12V-_P$36") (pintype "bidirectional"))
      (node (ref "U$1") (pin "P$37") (pinfunction "12V-_P$37") (pintype "bidirectional"))
      (node (ref "U$1") (pin "P$38") (pinfunction "12V-_P$38") (pintype "bidirectional"))
      (node (ref "U$1") (pin "P$39") (pinfunction "12V-_P$39") (pintype "bidirectional"))
      (node (ref "U$1") (pin "P$40") (pinfunction "12V-_P$40") (pintype "bidirectional"))
      (node (ref "U$1") (pin "P$41") (pinfunction "12V-_P$41") (pintype "bidirectional"))
      (node (ref "U$1") (pin "P$42") (pinfunction "12V-_P$42") (pintype "bidirectional"))
      (node (ref "U$1") (pin "P$43") (pinfunction "12V-_P$43") (pintype "bidirectional"))
      (node (ref "U$1") (pin "P$44") (pinfunction "12V-_P$44") (pintype "bidirectional"))
      (node (ref "U$1") (pin "P$45") (pinfunction "12V-_P$45") (pintype "bidirectional"))
      (node (ref "U$1") (pin "P$46") (pinfunction "12V-_P$46") (pintype "bidirectional"))
      (node (ref "U$1") (pin "P$47") (pinfunction "12V-_P$47") (pintype "bidirectional"))
      (node (ref "U$1") (pin "P$48") (pinfunction "12V-_P$48") (pintype "bidirectional"))
      (node (ref "U$1") (pin "P$49") (pinfunction "12V-_P$49") (pintype "bidirectional"))
      (node (ref "U$1") (pin "P$50") (pinfunction "12V-_P$50") (pintype "bidirectional"))
      (node (ref "U$1") (pin "P$52") (pinfunction "12V-_P$52") (pintype "bidirectional"))
      (node (ref "U$2") (pin "P$31") (pinfunction "12V-_P$31") (pintype "bidirectional"))
      (node (ref "U$2") (pin "P$32") (pinfunction "12V-_P$32") (pintype "bidirectional"))
      (node (ref "U$2") (pin "P$33") (pinfunction "12V-_P$33") (pintype "bidirectional"))
      (node (ref "U$2") (pin "P$34") (pinfunction "12V-_P$34") (pintype "bidirectional"))
      (node (ref "U$2") (pin "P$35") (pinfunction "12V-_P$35") (pintype "bidirectional"))
      (node (ref "U$2") (pin "P$36") (pinfunction "12V-_P$36") (pintype "bidirectional"))
      (node (ref "U$2") (pin "P$37") (pinfunction "12V-_P$37") (pintype "bidirectional"))
      (node (ref "U$2") (pin "P$38") (pinfunction "12V-_P$38") (pintype "bidirectional"))
      (node (ref "U$2") (pin "P$39") (pinfunction "12V-_P$39") (pintype "bidirectional"))
      (node (ref "U$2") (pin "P$40") (pinfunction "12V-_P$40") (pintype "bidirectional"))
      (node (ref "U$2") (pin "P$41") (pinfunction "12V-_P$41") (pintype "bidirectional"))
      (node (ref "U$2") (pin "P$42") (pinfunction "12V-_P$42") (pintype "bidirectional"))
      (node (ref "U$2") (pin "P$43") (pinfunction "12V-_P$43") (pintype "bidirectional"))
      (node (ref "U$2") (pin "P$44") (pinfunction "12V-_P$44") (pintype "bidirectional"))
      (node (ref "U$2") (pin "P$45") (pinfunction "12V-_P$45") (pintype "bidirectional"))
      (node (ref "U$2") (pin "P$46") (pinfunction "12V-_P$46") (pintype "bidirectional"))
      (node (ref "U$2") (pin "P$47") (pinfunction "12V-_P$47") (pintype "bidirectional"))
      (node (ref "U$2") (pin "P$48") (pinfunction "12V-_P$48") (pintype "bidirectional"))
      (node (ref "U$2") (pin "P$49") (pinfunction "12V-_P$49") (pintype "bidirectional"))
      (node (ref "U$2") (pin "P$50") (pinfunction "12V-_P$50") (pintype "bidirectional"))
      (node (ref "U$2") (pin "P$52") (pinfunction "12V-_P$52") (pintype "bidirectional"))
      (node (ref "U$3") (pin "P$31") (pinfunction "12V-_P$31") (pintype "bidirectional"))
      (node (ref "U$3") (pin "P$32") (pinfunction "12V-_P$32") (pintype "bidirectional"))
      (node (ref "U$3") (pin "P$33") (pinfunction "12V-_P$33") (pintype "bidirectional"))
      (node (ref "U$3") (pin "P$34") (pinfunction "12V-_P$34") (pintype "bidirectional"))
      (node (ref "U$3") (pin "P$35") (pinfunction "12V-_P$35") (pintype "bidirectional"))
      (node (ref "U$3") (pin "P$36") (pinfunction "12V-_P$36") (pintype "bidirectional"))
      (node (ref "U$3") (pin "P$37") (pinfunction "12V-_P$37") (pintype "bidirectional"))
      (node (ref "U$3") (pin "P$38") (pinfunction "12V-_P$38") (pintype "bidirectional"))
      (node (ref "U$3") (pin "P$39") (pinfunction "12V-_P$39") (pintype "bidirectional"))
      (node (ref "U$3") (pin "P$40") (pinfunction "12V-_P$40") (pintype "bidirectional"))
      (node (ref "U$3") (pin "P$41") (pinfunction "12V-_P$41") (pintype "bidirectional"))
      (node (ref "U$3") (pin "P$42") (pinfunction "12V-_P$42") (pintype "bidirectional"))
      (node (ref "U$3") (pin "P$43") (pinfunction "12V-_P$43") (pintype "bidirectional"))
      (node (ref "U$3") (pin "P$44") (pinfunction "12V-_P$44") (pintype "bidirectional"))
      (node (ref "U$3") (pin "P$45") (pinfunction "12V-_P$45") (pintype "bidirectional"))
      (node (ref "U$3") (pin "P$46") (pinfunction "12V-_P$46") (pintype "bidirectional"))
      (node (ref "U$3") (pin "P$47") (pinfunction "12V-_P$47") (pintype "bidirectional"))
      (node (ref "U$3") (pin "P$48") (pinfunction "12V-_P$48") (pintype "bidirectional"))
      (node (ref "U$3") (pin "P$49") (pinfunction "12V-_P$49") (pintype "bidirectional"))
      (node (ref "U$3") (pin "P$50") (pinfunction "12V-_P$50") (pintype "bidirectional"))
      (node (ref "U$3") (pin "P$52") (pinfunction "12V-_P$52") (pintype "bidirectional"))
      (node (ref "U$8") (pin "P$6") (pinfunction "P$6_P$6") (pintype "bidirectional"))
      (node (ref "U$9") (pin "P$1") (pinfunction "P$1_P$1") (pintype "bidirectional"))
      (node (ref "U$9") (pin "P$3") (pinfunction "P$3_P$3") (pintype "bidirectional"))
      (node (ref "U1") (pin "21") (pinfunction "AGND_21") (pintype "bidirectional"))
      (node (ref "U1") (pin "3") (pinfunction "GND_3") (pintype "bidirectional"))
      (node (ref "U1") (pin "5") (pinfunction "GND_5") (pintype "bidirectional"))
      (node (ref "U4") (pin "1") (pinfunction "A0_1") (pintype "bidirectional"))
      (node (ref "U4") (pin "14") (pinfunction "GND_14") (pintype "power_in"))
      (node (ref "U4") (pin "2") (pinfunction "A1_2") (pintype "bidirectional"))
      (node (ref "U4") (pin "24") (pinfunction "A5_24") (pintype "bidirectional"))
      (node (ref "U4") (pin "25") (pinfunction "EXTCLK_25") (pintype "input"))
      (node (ref "U4") (pin "3") (pinfunction "A2_3") (pintype "bidirectional"))
      (node (ref "U4") (pin "4") (pinfunction "A3_4") (pintype "bidirectional"))
      (node (ref "U4") (pin "5") (pinfunction "A4_5") (pintype "bidirectional"))
      (node (ref "U5") (pin "18") (pinfunction "GND18_18") (pintype "power_in"))
      (node (ref "U5") (pin "21") (pinfunction "GND21_21") (pintype "power_in"))
      (node (ref "U5") (pin "25") (pinfunction "AGND_25") (pintype "power_in"))
      (node (ref "U5") (pin "26") (pinfunction "TEST_26") (pintype "input"))
      (node (ref "U5") (pin "7") (pinfunction "GND7_7") (pintype "power_in"))
      (node (ref "U7") (pin "4") (pinfunction "GND_4") (pintype "bidirectional"))
      (node (ref "U7") (pin "TAB") (pinfunction "TABGND_TAB") (pintype "bidirectional"))
      (node (ref "V-_ESC1") (pin "P$1") (pinfunction "P$1_P$1") (pintype "bidirectional"))
      (node (ref "V-_ESC10") (pin "P$1") (pinfunction "P$1_P$1") (pintype "bidirectional"))
      (node (ref "V-_ESC11") (pin "P$1") (pinfunction "P$1_P$1") (pintype "bidirectional"))
      (node (ref "V-_ESC12") (pin "P$1") (pinfunction "P$1_P$1") (pintype "bidirectional"))
      (node (ref "V-_ESC2") (pin "P$1") (pinfunction "P$1_P$1") (pintype "bidirectional"))
      (node (ref "V-_ESC3") (pin "P$1") (pinfunction "P$1_P$1") (pintype "bidirectional"))
      (node (ref "V-_ESC4") (pin "P$1") (pinfunction "P$1_P$1") (pintype "bidirectional"))
      (node (ref "V-_ESC5") (pin "P$1") (pinfunction "P$1_P$1") (pintype "bidirectional"))
      (node (ref "V-_ESC6") (pin "P$1") (pinfunction "P$1_P$1") (pintype "bidirectional"))
      (node (ref "V-_ESC7") (pin "P$1") (pinfunction "P$1_P$1") (pintype "bidirectional"))
      (node (ref "V-_ESC8") (pin "P$1") (pinfunction "P$1_P$1") (pintype "bidirectional"))
      (node (ref "V-_ESC9") (pin "P$1") (pinfunction "P$1_P$1") (pintype "bidirectional"))
    )
    (net (code "20") (name "Net-(F1-Pad1)") (class "Default")
      (node (ref "F1") (pin "1") (pinfunction "1_1") (pintype "bidirectional"))
      (node (ref "V+_ESC1") (pin "P$1") (pinfunction "P$1_P$1") (pintype "bidirectional"))
    )
    (net (code "21") (name "Net-(F2-Pad1)") (class "Default")
      (node (ref "F2") (pin "1") (pinfunction "1_1") (pintype "bidirectional"))
      (node (ref "V+_ESC2") (pin "P$1") (pinfunction "P$1_P$1") (pintype "bidirectional"))
    )
    (net (code "22") (name "Net-(F3-Pad1)") (class "Default")
      (node (ref "F3") (pin "1") (pinfunction "1_1") (pintype "bidirectional"))
      (node (ref "V+_ESC3") (pin "P$1") (pinfunction "P$1_P$1") (pintype "bidirectional"))
    )
    (net (code "23") (name "Net-(F4-Pad1)") (class "Default")
      (node (ref "F4") (pin "1") (pinfunction "1_1") (pintype "bidirectional"))
      (node (ref "V+_ESC4") (pin "P$1") (pinfunction "P$1_P$1") (pintype "bidirectional"))
    )
    (net (code "24") (name "Net-(F5-Pad1)") (class "Default")
      (node (ref "F5") (pin "1") (pinfunction "1_1") (pintype "bidirectional"))
      (node (ref "V+_ESC5") (pin "P$1") (pinfunction "P$1_P$1") (pintype "bidirectional"))
    )
    (net (code "25") (name "Net-(F6-Pad1)") (class "Default")
      (node (ref "F6") (pin "1") (pinfunction "1_1") (pintype "bidirectional"))
      (node (ref "V+_ESC6") (pin "P$1") (pinfunction "P$1_P$1") (pintype "bidirectional"))
    )
    (net (code "26") (name "Net-(F7-Pad1)") (class "Default")
      (node (ref "F7") (pin "1") (pinfunction "1_1") (pintype "bidirectional"))
      (node (ref "V+_ESC7") (pin "P$1") (pinfunction "P$1_P$1") (pintype "bidirectional"))
    )
    (net (code "27") (name "Net-(F8-Pad1)") (class "Default")
      (node (ref "F8") (pin "1") (pinfunction "1_1") (pintype "bidirectional"))
      (node (ref "V+_ESC8") (pin "P$1") (pinfunction "P$1_P$1") (pintype "bidirectional"))
    )
    (net (code "28") (name "Net-(F9-Pad1)") (class "Default")
      (node (ref "F9") (pin "1") (pinfunction "1_1") (pintype "bidirectional"))
      (node (ref "V+_ESC9") (pin "P$1") (pinfunction "P$1_P$1") (pintype "bidirectional"))
    )
    (net (code "29") (name "Net-(F10-Pad1)") (class "Default")
      (node (ref "F10") (pin "1") (pinfunction "1_1") (pintype "bidirectional"))
      (node (ref "V+_ESC10") (pin "P$1") (pinfunction "P$1_P$1") (pintype "bidirectional"))
    )
    (net (code "30") (name "Net-(F11-Pad1)") (class "Default")
      (node (ref "F11") (pin "1") (pinfunction "1_1") (pintype "bidirectional"))
      (node (ref "V+_ESC11") (pin "P$1") (pinfunction "P$1_P$1") (pintype "bidirectional"))
    )
    (net (code "31") (name "Net-(F12-Pad1)") (class "Default")
      (node (ref "F12") (pin "1") (pinfunction "1_1") (pintype "bidirectional"))
      (node (ref "V+_ESC12") (pin "P$1") (pinfunction "P$1_P$1") (pintype "bidirectional"))
    )
    (net (code "32") (name "Net-(LED1-PadA)") (class "Default")
      (node (ref "LED1") (pin "A") (pinfunction "A_A") (pintype "passive"))
      (node (ref "R4") (pin "1") (pinfunction "1_1") (pintype "passive"))
    )
    (net (code "33") (name "Net-(LED2-PadA)") (class "Default")
      (node (ref "LED2") (pin "A") (pinfunction "A_A") (pintype "passive"))
      (node (ref "R5") (pin "1") (pinfunction "1_1") (pintype "passive"))
    )
    (net (code "34") (name "Net-(LED3-PadA)") (class "Default")
      (node (ref "LED3") (pin "A") (pinfunction "A_A") (pintype "passive"))
      (node (ref "R10") (pin "1") (pinfunction "1_1") (pintype "passive"))
    )
    (net (code "35") (name "Net-(LED4-PadA)") (class "Default")
      (node (ref "LED4") (pin "A") (pinfunction "A_A") (pintype "passive"))
      (node (ref "R11") (pin "1") (pinfunction "1_1") (pintype "passive"))
    )
    (net (code "36") (name "Net-(U$4-A)") (class "Default")
      (node (ref "R1") (pin "2") (pinfunction "2_2") (pintype "passive"))
      (node (ref "U$4") (pin "1") (pinfunction "A_1") (pintype "passive"))
      (node (ref "U$7") (pin "1") (pinfunction "G_1") (pintype "passive"))
    )
    (net (code "37") (name "Net-(U$4-C)") (class "Default")
      (node (ref "U$4") (pin "3") (pinfunction "C_3") (pintype "passive"))
      (node (ref "U$6") (pin "1") (pinfunction "A_1") (pintype "passive"))
    )
    (net (code "38") (name "Net-(U$10-1)") (class "Default")
      (node (ref "C7") (pin "2") (pinfunction "2_2") (pintype "passive"))
      (node (ref "U$10") (pin "P$1") (pinfunction "1_P$1") (pintype "passive"))
      (node (ref "U$9") (pin "P$4") (pinfunction "P$4_P$4") (pintype "bidirectional"))
      (node (ref "U7") (pin "1") (pinfunction "OUTPUT_1") (pintype "bidirectional"))
    )
    (net (code "39") (name "Net-(U1-PB3(MOSI{slash}OC2))") (class "Default")
      (node (ref "U$8") (pin "P$7") (pinfunction "P$7_P$7") (pintype "bidirectional"))
      (node (ref "U1") (pin "15") (pinfunction "PB3(MOSI/OC2)_15") (pintype "bidirectional"))
    )
    (net (code "40") (name "Net-(U1-PB4(MISO))") (class "Default")
      (node (ref "U$8") (pin "P$1") (pinfunction "P$1_P$1") (pintype "bidirectional"))
      (node (ref "U1") (pin "16") (pinfunction "PB4(MISO)_16") (pintype "bidirectional"))
    )
    (net (code "41") (name "Net-(U1-PB5(SCK))") (class "Default")
      (node (ref "U$8") (pin "P$2") (pinfunction "P$2_P$2") (pintype "bidirectional"))
      (node (ref "U1") (pin "17") (pinfunction "PB5(SCK)_17") (pintype "bidirectional"))
    )
    (net (code "42") (name "Net-(U1-PC6({slash}RESET))") (class "Default")
      (node (ref "R3") (pin "2") (pinfunction "2_2") (pintype "passive"))
      (node (ref "U$8") (pin "P$3") (pinfunction "P$3_P$3") (pintype "bidirectional"))
      (node (ref "U1") (pin "29") (pinfunction "PC6(/RESET)_29") (pintype "bidirectional"))
    )
    (net (code "43") (name "Net-(U4-#OE)") (class "Default")
      (node (ref "R7") (pin "2") (pinfunction "2_2") (pintype "passive"))
      (node (ref "U4") (pin "23") (pinfunction "#OE_23") (pintype "input"))
    )
    (net (code "44") (name "Net-(U4-PWM0)") (class "Default")
      (node (ref "P1") (pin "1") (pinfunction "1_1") (pintype "passive"))
      (node (ref "U4") (pin "6") (pinfunction "PWM0_6") (pintype "output"))
    )
    (net (code "45") (name "Net-(U4-PWM1)") (class "Default")
      (node (ref "P2") (pin "1") (pinfunction "1_1") (pintype "passive"))
      (node (ref "U4") (pin "7") (pinfunction "PWM1_7") (pintype "output"))
    )
    (net (code "46") (name "Net-(U4-PWM2)") (class "Default")
      (node (ref "P3") (pin "1") (pinfunction "1_1") (pintype "passive"))
      (node (ref "U4") (pin "8") (pinfunction "PWM2_8") (pintype "output"))
    )
    (net (code "47") (name "Net-(U4-PWM3)") (class "Default")
      (node (ref "P4") (pin "1") (pinfunction "1_1") (pintype "passive"))
      (node (ref "U4") (pin "9") (pinfunction "PWM3_9") (pintype "output"))
    )
    (net (code "48") (name "Net-(U4-PWM4)") (class "Default")
      (node (ref "P5") (pin "1") (pinfunction "1_1") (pintype "passive"))
      (node (ref "U4") (pin "10") (pinfunction "PWM4_10") (pintype "output"))
    )
    (net (code "49") (name "Net-(U4-PWM5)") (class "Default")
      (node (ref "P6") (pin "1") (pinfunction "1_1") (pintype "passive"))
      (node (ref "U4") (pin "11") (pinfunction "PWM5_11") (pintype "output"))
    )
    (net (code "50") (name "Net-(U4-PWM6)") (class "Default")
      (node (ref "P7") (pin "1") (pinfunction "1_1") (pintype "passive"))
      (node (ref "U4") (pin "12") (pinfunction "PWM6_12") (pintype "output"))
    )
    (net (code "51") (name "Net-(U4-PWM7)") (class "Default")
      (node (ref "P8") (pin "1") (pinfunction "1_1") (pintype "passive"))
      (node (ref "U4") (pin "13") (pinfunction "PWM7_13") (pintype "output"))
    )
    (net (code "52") (name "Net-(U4-PWM8)") (class "Default")
      (node (ref "P9") (pin "1") (pinfunction "1_1") (pintype "passive"))
      (node (ref "U4") (pin "15") (pinfunction "PWM8_15") (pintype "output"))
    )
    (net (code "53") (name "Net-(U4-PWM9)") (class "Default")
      (node (ref "P10") (pin "1") (pinfunction "1_1") (pintype "passive"))
      (node (ref "U4") (pin "16") (pinfunction "PWM9_16") (pintype "output"))
    )
    (net (code "54") (name "Net-(U4-PWM10)") (class "Default")
      (node (ref "P11") (pin "1") (pinfunction "1_1") (pintype "passive"))
      (node (ref "U4") (pin "17") (pinfunction "PWM10_17") (pintype "output"))
    )
    (net (code "55") (name "Net-(U4-PWM11)") (class "Default")
      (node (ref "P12") (pin "1") (pinfunction "1_1") (pintype "passive"))
      (node (ref "U4") (pin "18") (pinfunction "PWM11_18") (pintype "output"))
    )
    (net (code "56") (name "Net-(U5-3V3OUT)") (class "Default")
      (node (ref "C4") (pin "1") (pinfunction "1_1") (pintype "passive"))
      (node (ref "U5") (pin "17") (pinfunction "3V3OUT_17") (pintype "output"))
    )
    (net (code "57") (name "Net-(U5-RESET)") (class "Default")
      (node (ref "R9") (pin "1") (pinfunction "1_1") (pintype "passive"))
      (node (ref "U5") (pin "19") (pinfunction "RESET_19") (pintype "input"))
    )
    (net (code "58") (name "Net-(U7-BOOST)") (class "Default")
      (node (ref "C7") (pin "1") (pinfunction "1_1") (pintype "passive"))
      (node (ref "U7") (pin "3") (pinfunction "BOOST_3") (pintype "bidirectional"))
    )
    (net (code "59") (name "V+") (class "Default")
      (node (ref "R11") (pin "2") (pinfunction "2_2") (pintype "passive"))
      (node (ref "R2") (pin "2") (pinfunction "2_2") (pintype "passive"))
      (node (ref "U$1") (pin "P$26") (pinfunction "48V+_P$26") (pintype "bidirectional"))
      (node (ref "U$1") (pin "P$27") (pinfunction "48V+_P$27") (pintype "bidirectional"))
      (node (ref "U$1") (pin "P$28") (pinfunction "48V+_P$28") (pintype "bidirectional"))
      (node (ref "U$1") (pin "P$29") (pinfunction "48V+_P$29") (pintype "bidirectional"))
      (node (ref "U$1") (pin "P$30") (pinfunction "48V+_P$30") (pintype "bidirectional"))
      (node (ref "U$2") (pin "P$26") (pinfunction "48V+_P$26") (pintype "bidirectional"))
      (node (ref "U$2") (pin "P$27") (pinfunction "48V+_P$27") (pintype "bidirectional"))
      (node (ref "U$2") (pin "P$28") (pinfunction "48V+_P$28") (pintype "bidirectional"))
      (node (ref "U$2") (pin "P$29") (pinfunction "48V+_P$29") (pintype "bidirectional"))
      (node (ref "U$2") (pin "P$30") (pinfunction "48V+_P$30") (pintype "bidirectional"))
      (node (ref "U$3") (pin "P$26") (pinfunction "48V+_P$26") (pintype "bidirectional"))
      (node (ref "U$3") (pin "P$27") (pinfunction "48V+_P$27") (pintype "bidirectional"))
      (node (ref "U$3") (pin "P$28") (pinfunction "48V+_P$28") (pintype "bidirectional"))
      (node (ref "U$3") (pin "P$29") (pinfunction "48V+_P$29") (pintype "bidirectional"))
      (node (ref "U$3") (pin "P$30") (pinfunction "48V+_P$30") (pintype "bidirectional"))
      (node (ref "U$6") (pin "3") (pinfunction "C_3") (pintype "passive"))
      (node (ref "V+_CONN") (pin "P$1") (pinfunction "1_P$1") (pintype "passive"))
    )
    (net (code "60") (name "V-") (class "Default")
      (node (ref "LED4") (pin "C") (pinfunction "C_C") (pintype "passive"))
      (node (ref "R1") (pin "1") (pinfunction "1_1") (pintype "passive"))
      (node (ref "U$1") (pin "P$21") (pinfunction "48V-_P$21") (pintype "bidirectional"))
      (node (ref "U$1") (pin "P$22") (pinfunction "48V-_P$22") (pintype "bidirectional"))
      (node (ref "U$1") (pin "P$23") (pinfunction "48V-_P$23") (pintype "bidirectional"))
      (node (ref "U$1") (pin "P$24") (pinfunction "48V-_P$24") (pintype "bidirectional"))
      (node (ref "U$1") (pin "P$25") (pinfunction "48V-_P$25") (pintype "bidirectional"))
      (node (ref "U$2") (pin "P$21") (pinfunction "48V-_P$21") (pintype "bidirectional"))
      (node (ref "U$2") (pin "P$22") (pinfunction "48V-_P$22") (pintype "bidirectional"))
      (node (ref "U$2") (pin "P$23") (pinfunction "48V-_P$23") (pintype "bidirectional"))
      (node (ref "U$2") (pin "P$24") (pinfunction "48V-_P$24") (pintype "bidirectional"))
      (node (ref "U$2") (pin "P$25") (pinfunction "48V-_P$25") (pintype "bidirectional"))
      (node (ref "U$3") (pin "P$21") (pinfunction "48V-_P$21") (pintype "bidirectional"))
      (node (ref "U$3") (pin "P$22") (pinfunction "48V-_P$22") (pintype "bidirectional"))
      (node (ref "U$3") (pin "P$23") (pinfunction "48V-_P$23") (pintype "bidirectional"))
      (node (ref "U$3") (pin "P$24") (pinfunction "48V-_P$24") (pintype "bidirectional"))
      (node (ref "U$3") (pin "P$25") (pinfunction "48V-_P$25") (pintype "bidirectional"))
      (node (ref "U$5") (pin "1") (pinfunction "A_1") (pintype "passive"))
      (node (ref "U$7") (pin "3") (pinfunction "S_3") (pintype "passive"))
      (node (ref "V-_CONN") (pin "P$1") (pinfunction "1_P$1") (pintype "passive"))
    )
    (net (code "61") (name "VCC") (class "Default")
      (node (ref "C11") (pin "+") (pinfunction "+_+") (pintype "passive"))
      (node (ref "C12") (pin "+") (pinfunction "+_+") (pintype "passive"))
      (node (ref "C13") (pin "+") (pinfunction "+_+") (pintype "passive"))
      (node (ref "C14") (pin "+") (pinfunction "+_+") (pintype "passive"))
      (node (ref "C3") (pin "1") (pinfunction "1_1") (pintype "passive"))
      (node (ref "CAMDATA") (pin "1") (pinfunction "1_1") (pintype "bidirectional"))
      (node (ref "CAMDATA1") (pin "3") (pinfunction "3_3") (pintype "bidirectional"))
      (node (ref "CAMDATA1") (pin "4") (pinfunction "4_4") (pintype "bidirectional"))
      (node (ref "CAMDATA2") (pin "3") (pinfunction "3_3") (pintype "bidirectional"))
      (node (ref "CAMDATA2") (pin "4") (pinfunction "4_4") (pintype "bidirectional"))
      (node (ref "F1") (pin "2") (pinfunction "2_2") (pintype "bidirectional"))
      (node (ref "F10") (pin "2") (pinfunction "2_2") (pintype "bidirectional"))
      (node (ref "F11") (pin "2") (pinfunction "2_2") (pintype "bidirectional"))
      (node (ref "F12") (pin "2") (pinfunction "2_2") (pintype "bidirectional"))
      (node (ref "F2") (pin "2") (pinfunction "2_2") (pintype "bidirectional"))
      (node (ref "F3") (pin "2") (pinfunction "2_2") (pintype "bidirectional"))
      (node (ref "F4") (pin "2") (pinfunction "2_2") (pintype "bidirectional"))
      (node (ref "F5") (pin "2") (pinfunction "2_2") (pintype "bidirectional"))
      (node (ref "F6") (pin "2") (pinfunction "2_2") (pintype "bidirectional"))
      (node (ref "F7") (pin "2") (pinfunction "2_2") (pintype "bidirectional"))
      (node (ref "F8") (pin "2") (pinfunction "2_2") (pintype "bidirectional"))
      (node (ref "F9") (pin "2") (pinfunction "2_2") (pintype "bidirectional"))
      (node (ref "R10") (pin "2") (pinfunction "2_2") (pintype "passive"))
      (node (ref "U$1") (pin "P$1") (pinfunction "12V+_P$1") (pintype "bidirectional"))
      (node (ref "U$1") (pin "P$10") (pinfunction "12V+_P$10") (pintype "bidirectional"))
      (node (ref "U$1") (pin "P$11") (pinfunction "12V+_P$11") (pintype "bidirectional"))
      (node (ref "U$1") (pin "P$12") (pinfunction "12V+_P$12") (pintype "bidirectional"))
      (node (ref "U$1") (pin "P$13") (pinfunction "12V+_P$13") (pintype "bidirectional"))
      (node (ref "U$1") (pin "P$14") (pinfunction "12V+_P$14") (pintype "bidirectional"))
      (node (ref "U$1") (pin "P$15") (pinfunction "12V+_P$15") (pintype "bidirectional"))
      (node (ref "U$1") (pin "P$16") (pinfunction "12V+_P$16") (pintype "bidirectional"))
      (node (ref "U$1") (pin "P$17") (pinfunction "12V+_P$17") (pintype "bidirectional"))
      (node (ref "U$1") (pin "P$18") (pinfunction "12V+_P$18") (pintype "bidirectional"))
      (node (ref "U$1") (pin "P$19") (pinfunction "12V+_P$19") (pintype "bidirectional"))
      (node (ref "U$1") (pin "P$2") (pinfunction "12V+_P$2") (pintype "bidirectional"))
      (node (ref "U$1") (pin "P$20") (pinfunction "12V+_P$20") (pintype "bidirectional"))
      (node (ref "U$1") (pin "P$3") (pinfunction "12V+_P$3") (pintype "bidirectional"))
      (node (ref "U$1") (pin "P$4") (pinfunction "12V+_P$4") (pintype "bidirectional"))
      (node (ref "U$1") (pin "P$5") (pinfunction "12V+_P$5") (pintype "bidirectional"))
      (node (ref "U$1") (pin "P$6") (pinfunction "12V+_P$6") (pintype "bidirectional"))
      (node (ref "U$1") (pin "P$7") (pinfunction "12V+_P$7") (pintype "bidirectional"))
      (node (ref "U$1") (pin "P$8") (pinfunction "12V+_P$8") (pintype "bidirectional"))
      (node (ref "U$1") (pin "P$9") (pinfunction "12V+_P$9") (pintype "bidirectional"))
      (node (ref "U$2") (pin "P$1") (pinfunction "12V+_P$1") (pintype "bidirectional"))
      (node (ref "U$2") (pin "P$10") (pinfunction "12V+_P$10") (pintype "bidirectional"))
      (node (ref "U$2") (pin "P$11") (pinfunction "12V+_P$11") (pintype "bidirectional"))
      (node (ref "U$2") (pin "P$12") (pinfunction "12V+_P$12") (pintype "bidirectional"))
      (node (ref "U$2") (pin "P$13") (pinfunction "12V+_P$13") (pintype "bidirectional"))
      (node (ref "U$2") (pin "P$14") (pinfunction "12V+_P$14") (pintype "bidirectional"))
      (node (ref "U$2") (pin "P$15") (pinfunction "12V+_P$15") (pintype "bidirectional"))
      (node (ref "U$2") (pin "P$16") (pinfunction "12V+_P$16") (pintype "bidirectional"))
      (node (ref "U$2") (pin "P$17") (pinfunction "12V+_P$17") (pintype "bidirectional"))
      (node (ref "U$2") (pin "P$18") (pinfunction "12V+_P$18") (pintype "bidirectional"))
      (node (ref "U$2") (pin "P$19") (pinfunction "12V+_P$19") (pintype "bidirectional"))
      (node (ref "U$2") (pin "P$2") (pinfunction "12V+_P$2") (pintype "bidirectional"))
      (node (ref "U$2") (pin "P$20") (pinfunction "12V+_P$20") (pintype "bidirectional"))
      (node (ref "U$2") (pin "P$3") (pinfunction "12V+_P$3") (pintype "bidirectional"))
      (node (ref "U$2") (pin "P$4") (pinfunction "12V+_P$4") (pintype "bidirectional"))
      (node (ref "U$2") (pin "P$5") (pinfunction "12V+_P$5") (pintype "bidirectional"))
      (node (ref "U$2") (pin "P$6") (pinfunction "12V+_P$6") (pintype "bidirectional"))
      (node (ref "U$2") (pin "P$7") (pinfunction "12V+_P$7") (pintype "bidirectional"))
      (node (ref "U$2") (pin "P$8") (pinfunction "12V+_P$8") (pintype "bidirectional"))
      (node (ref "U$2") (pin "P$9") (pinfunction "12V+_P$9") (pintype "bidirectional"))
      (node (ref "U$3") (pin "P$1") (pinfunction "12V+_P$1") (pintype "bidirectional"))
      (node (ref "U$3") (pin "P$10") (pinfunction "12V+_P$10") (pintype "bidirectional"))
      (node (ref "U$3") (pin "P$11") (pinfunction "12V+_P$11") (pintype "bidirectional"))
      (node (ref "U$3") (pin "P$12") (pinfunction "12V+_P$12") (pintype "bidirectional"))
      (node (ref "U$3") (pin "P$13") (pinfunction "12V+_P$13") (pintype "bidirectional"))
      (node (ref "U$3") (pin "P$14") (pinfunction "12V+_P$14") (pintype "bidirectional"))
      (node (ref "U$3") (pin "P$15") (pinfunction "12V+_P$15") (pintype "bidirectional"))
      (node (ref "U$3") (pin "P$16") (pinfunction "12V+_P$16") (pintype "bidirectional"))
      (node (ref "U$3") (pin "P$17") (pinfunction "12V+_P$17") (pintype "bidirectional"))
      (node (ref "U$3") (pin "P$18") (pinfunction "12V+_P$18") (pintype "bidirectional"))
      (node (ref "U$3") (pin "P$19") (pinfunction "12V+_P$19") (pintype "bidirectional"))
      (node (ref "U$3") (pin "P$2") (pinfunction "12V+_P$2") (pintype "bidirectional"))
      (node (ref "U$3") (pin "P$20") (pinfunction "12V+_P$20") (pintype "bidirectional"))
      (node (ref "U$3") (pin "P$3") (pinfunction "12V+_P$3") (pintype "bidirectional"))
      (node (ref "U$3") (pin "P$4") (pinfunction "12V+_P$4") (pintype "bidirectional"))
      (node (ref "U$3") (pin "P$5") (pinfunction "12V+_P$5") (pintype "bidirectional"))
      (node (ref "U$3") (pin "P$6") (pinfunction "12V+_P$6") (pintype "bidirectional"))
      (node (ref "U$3") (pin "P$7") (pinfunction "12V+_P$7") (pintype "bidirectional"))
      (node (ref "U$3") (pin "P$8") (pinfunction "12V+_P$8") (pintype "bidirectional"))
      (node (ref "U$3") (pin "P$9") (pinfunction "12V+_P$9") (pintype "bidirectional"))
      (node (ref "U7") (pin "2") (pinfunction "VIN_2") (pintype "bidirectional"))
    )
    (net (code "62") (name "unconnected-(U$8-PadP$4)") (class "Default")
      (node (ref "U$8") (pin "P$4") (pinfunction "P$4_P$4") (pintype "bidirectional"))
    )
    (net (code "63") (name "unconnected-(U$8-PadP$5)") (class "Default")
      (node (ref "U$8") (pin "P$5") (pinfunction "P$5_P$5") (pintype "bidirectional"))
    )
    (net (code "64") (name "unconnected-(U1-ADC6-Pad19)") (class "Default")
      (node (ref "U1") (pin "19") (pinfunction "ADC6_19") (pintype "bidirectional"))
    )
    (net (code "65") (name "unconnected-(U1-ADC7-Pad22)") (class "Default")
      (node (ref "U1") (pin "22") (pinfunction "ADC7_22") (pintype "bidirectional"))
    )
    (net (code "66") (name "unconnected-(U1-PB0(ICP)-Pad12)") (class "Default")
      (node (ref "U1") (pin "12") (pinfunction "PB0(ICP)_12") (pintype "bidirectional"))
    )
    (net (code "67") (name "unconnected-(U1-PB2(SS{slash}OC1B)-Pad14)") (class "Default")
      (node (ref "U1") (pin "14") (pinfunction "PB2(SS/OC1B)_14") (pintype "bidirectional"))
    )
    (net (code "68") (name "unconnected-(U1-PB6(XTAL1{slash}TOSC1)-Pad7)") (class "Default")
      (node (ref "U1") (pin "7") (pinfunction "PB6(XTAL1/TOSC1)_7") (pintype "bidirectional"))
    )
    (net (code "69") (name "unconnected-(U1-PB7(XTAL2{slash}TOSC2)-Pad8)") (class "Default")
      (node (ref "U1") (pin "8") (pinfunction "PB7(XTAL2/TOSC2)_8") (pintype "bidirectional"))
    )
    (net (code "70") (name "unconnected-(U1-PC0(ADC0)-Pad23)") (class "Default")
      (node (ref "U1") (pin "23") (pinfunction "PC0(ADC0)_23") (pintype "bidirectional"))
    )
    (net (code "71") (name "unconnected-(U1-PC1(ADC1)-Pad24)") (class "Default")
      (node (ref "U1") (pin "24") (pinfunction "PC1(ADC1)_24") (pintype "bidirectional"))
    )
    (net (code "72") (name "unconnected-(U1-PC2(ADC2)-Pad25)") (class "Default")
      (node (ref "U1") (pin "25") (pinfunction "PC2(ADC2)_25") (pintype "bidirectional"))
    )
    (net (code "73") (name "unconnected-(U1-PD3(INT1)-Pad1)") (class "Default")
      (node (ref "U1") (pin "1") (pinfunction "PD3(INT1)_1") (pintype "bidirectional"))
    )
    (net (code "74") (name "unconnected-(U1-PD4(XCK{slash}T0)-Pad2)") (class "Default")
      (node (ref "U1") (pin "2") (pinfunction "PD4(XCK/T0)_2") (pintype "bidirectional"))
    )
    (net (code "75") (name "unconnected-(U1-PD5(T1)-Pad9)") (class "Default")
      (node (ref "U1") (pin "9") (pinfunction "PD5(T1)_9") (pintype "bidirectional"))
    )
    (net (code "76") (name "unconnected-(U1-PD6(AIN0)-Pad10)") (class "Default")
      (node (ref "U1") (pin "10") (pinfunction "PD6(AIN0)_10") (pintype "bidirectional"))
    )
    (net (code "77") (name "unconnected-(U1-PD7(AIN1)-Pad11)") (class "Default")
      (node (ref "U1") (pin "11") (pinfunction "PD7(AIN1)_11") (pintype "bidirectional"))
    )
    (net (code "78") (name "unconnected-(U4-PWM13-Pad20)") (class "Default")
      (node (ref "U4") (pin "20") (pinfunction "PWM13_20") (pintype "output"))
    )
    (net (code "79") (name "unconnected-(U4-PWM14-Pad21)") (class "Default")
      (node (ref "U4") (pin "21") (pinfunction "PWM14_21") (pintype "output"))
    )
    (net (code "80") (name "unconnected-(U4-PWM15-Pad22)") (class "Default")
      (node (ref "U4") (pin "22") (pinfunction "PWM15_22") (pintype "output"))
    )
    (net (code "81") (name "unconnected-(U5-DCD-Pad10)") (class "Default")
      (node (ref "U5") (pin "10") (pinfunction "DCD_10") (pintype "input"))
    )
    (net (code "82") (name "unconnected-(U5-DSR-Pad9)") (class "Default")
      (node (ref "U5") (pin "9") (pinfunction "DSR_9") (pintype "input"))
    )
    (net (code "83") (name "unconnected-(U5-OSCI-Pad27)") (class "Default")
      (node (ref "U5") (pin "27") (pinfunction "OSCI_27") (pintype "input"))
    )
    (net (code "84") (name "unconnected-(U5-OSCO-Pad28)") (class "Default")
      (node (ref "U5") (pin "28") (pinfunction "OSCO_28") (pintype "output"))
    )
    (net (code "85") (name "unconnected-(U5-PWREN-Pad14)") (class "Default")
      (node (ref "U5") (pin "14") (pinfunction "PWREN_14") (pintype "input"))
    )
    (net (code "86") (name "unconnected-(U5-RI-Pad6)") (class "Default")
      (node (ref "U5") (pin "6") (pinfunction "RI_6") (pintype "input"))
    )
    (net (code "87") (name "unconnected-(U5-RTS-Pad3)") (class "Default")
      (node (ref "U5") (pin "3") (pinfunction "RTS_3") (pintype "output"))
    )
    (net (code "88") (name "unconnected-(U5-SLEEP-Pad12)") (class "Default")
      (node (ref "U5") (pin "12") (pinfunction "SLEEP_12") (pintype "input"))
    )
    (net (code "89") (name "unconnected-(U5-TXDEN-Pad13)") (class "Default")
      (node (ref "U5") (pin "13") (pinfunction "TXDEN_13") (pintype "input"))
    )
    (net (code "90") (name "unconnected-(U7-NC1-Pad5)") (class "Default")
      (node (ref "U7") (pin "5") (pinfunction "NC1_5") (pintype "no_connect"))
    )
    (net (code "91") (name "unconnected-(U7-ON{slash}OFF-Pad7)") (class "Default")
      (node (ref "U7") (pin "7") (pinfunction "ON/OFF_7") (pintype "bidirectional"))
    )
  )
)
